# Sheet1.net
KiCad netlist of a schematic drawn in Altium Designer
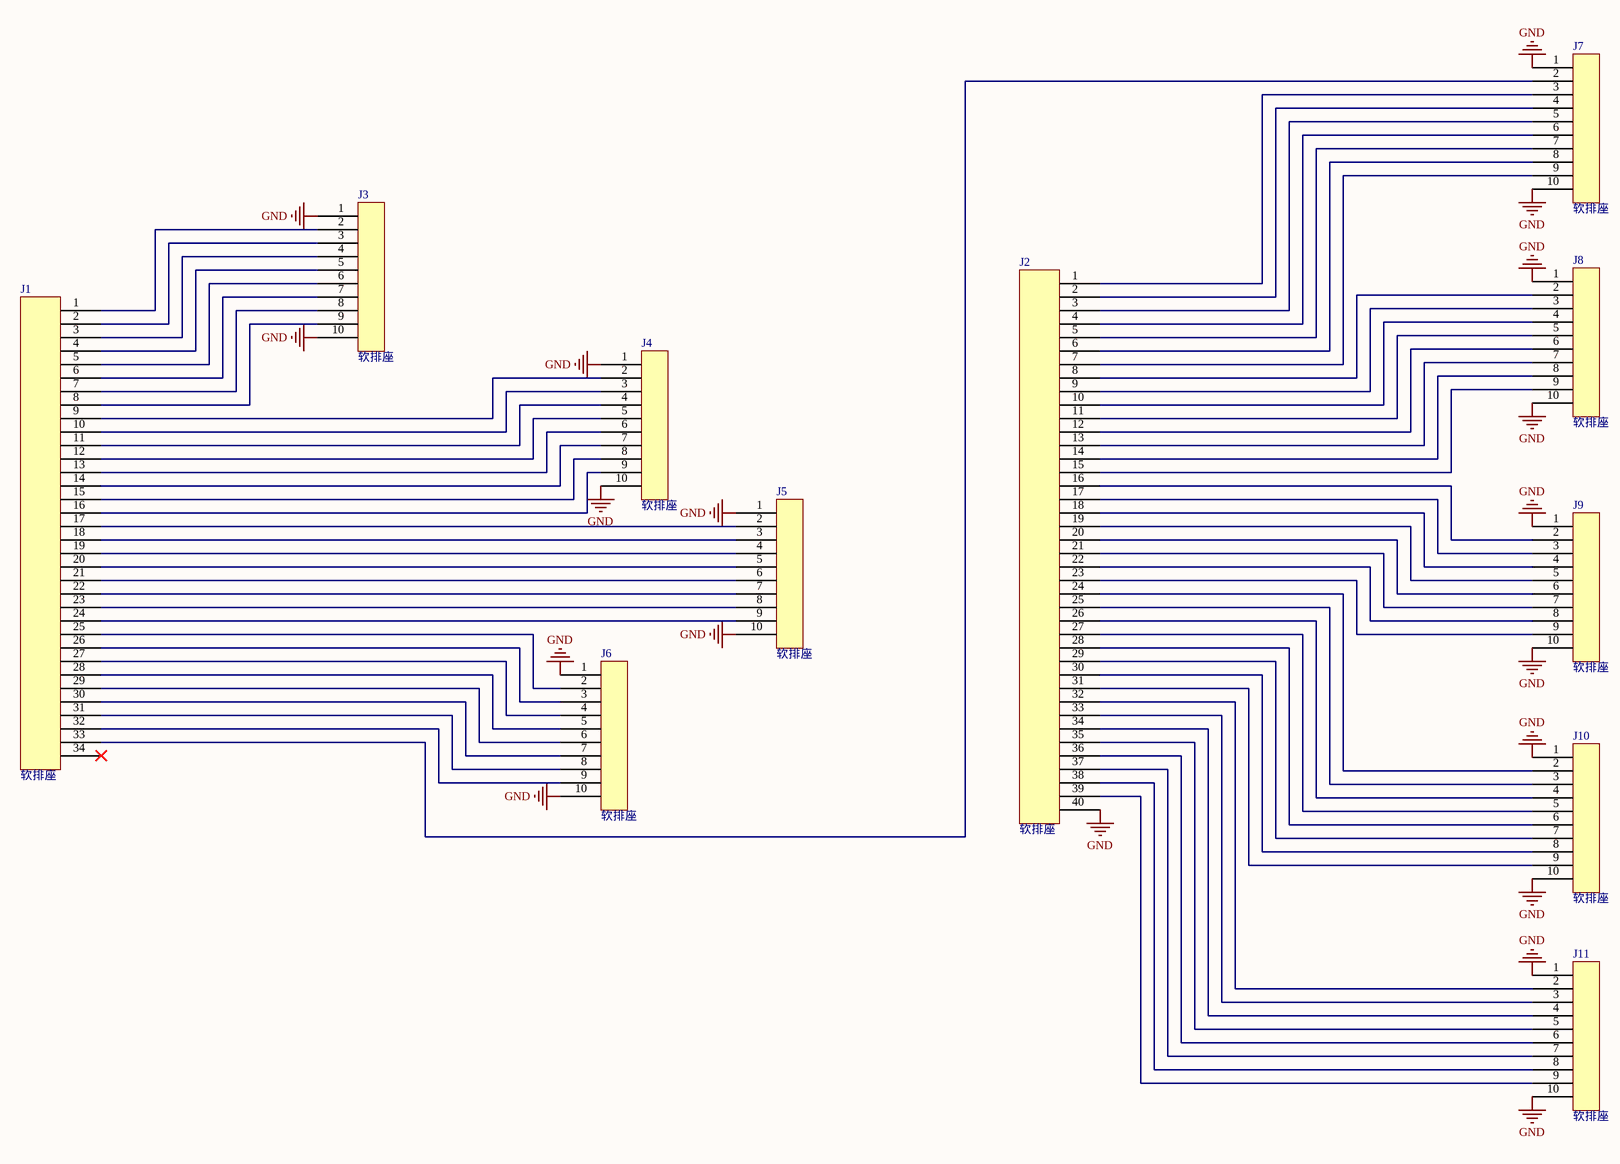
[diagram p0: Sheet1.SchDoc]

(export (version "E")
  (design (tool "Eeschema 10.0.6"))
  (components
    (comp (ref "J1") (value "软排座") (footprint "34P软排线") (libsource (lib "My") (part "34P")))
    (comp (ref "J2") (value "软排座") (footprint "40P软排线") (libsource (lib "My") (part "40P")))
    (comp (ref "J3") (value "软排座") (footprint "10P软排线(逆)") (libsource (lib "My") (part "10P")))
    (comp (ref "J4") (value "软排座") (footprint "10P软排线(逆)") (libsource (lib "My") (part "10P")))
    (comp (ref "J5") (value "软排座") (footprint "10P软排线(逆)") (libsource (lib "My") (part "10P")))
    (comp (ref "J6") (value "软排座") (footprint "10P软排线(逆)") (libsource (lib "My") (part "10P")))
    (comp (ref "J7") (value "软排座") (footprint "10P软排线") (libsource (lib "My") (part "10P")))
    (comp (ref "J8") (value "软排座") (footprint "10P软排线") (libsource (lib "My") (part "10P")))
    (comp (ref "J9") (value "软排座") (footprint "10P软排线") (libsource (lib "My") (part "10P")))
    (comp (ref "J10") (value "软排座") (footprint "10P软排线") (libsource (lib "My") (part "10P")))
    (comp (ref "J11") (value "软排座") (footprint "10P软排线") (libsource (lib "My") (part "10P")))
  )
  (nets
    (net (code "1") (name "GND") (class "Default")
      (node (ref "J10") (pin "1") (pinfunction "1_1") (pintype "passive"))
      (node (ref "J10") (pin "10") (pinfunction "10_10") (pintype "passive"))
      (node (ref "J11") (pin "1") (pinfunction "1_1") (pintype "passive"))
      (node (ref "J11") (pin "10") (pinfunction "10_10") (pintype "passive"))
      (node (ref "J2") (pin "40") (pinfunction "40_40") (pintype "passive"))
      (node (ref "J3") (pin "1") (pinfunction "1_1") (pintype "passive"))
      (node (ref "J3") (pin "10") (pinfunction "10_10") (pintype "passive"))
      (node (ref "J4") (pin "1") (pinfunction "1_1") (pintype "passive"))
      (node (ref "J4") (pin "10") (pinfunction "10_10") (pintype "passive"))
      (node (ref "J5") (pin "1") (pinfunction "1_1") (pintype "passive"))
      (node (ref "J5") (pin "10") (pinfunction "10_10") (pintype "passive"))
      (node (ref "J6") (pin "1") (pinfunction "1_1") (pintype "passive"))
      (node (ref "J6") (pin "10") (pinfunction "10_10") (pintype "passive"))
      (node (ref "J7") (pin "1") (pinfunction "1_1") (pintype "passive"))
      (node (ref "J7") (pin "10") (pinfunction "10_10") (pintype "passive"))
      (node (ref "J8") (pin "1") (pinfunction "1_1") (pintype "passive"))
      (node (ref "J8") (pin "10") (pinfunction "10_10") (pintype "passive"))
      (node (ref "J9") (pin "1") (pinfunction "1_1") (pintype "passive"))
      (node (ref "J9") (pin "10") (pinfunction "10_10") (pintype "passive"))
    )
    (net (code "2") (name "Net-(J1-Pad1)") (class "Default")
      (node (ref "J1") (pin "1") (pinfunction "1_1") (pintype "passive"))
      (node (ref "J3") (pin "2") (pinfunction "2_2") (pintype "passive"))
    )
    (net (code "3") (name "Net-(J1-Pad2)") (class "Default")
      (node (ref "J1") (pin "2") (pinfunction "2_2") (pintype "passive"))
      (node (ref "J3") (pin "3") (pinfunction "3_3") (pintype "passive"))
    )
    (net (code "4") (name "Net-(J1-Pad3)") (class "Default")
      (node (ref "J1") (pin "3") (pinfunction "3_3") (pintype "passive"))
      (node (ref "J3") (pin "4") (pinfunction "4_4") (pintype "passive"))
    )
    (net (code "5") (name "Net-(J1-Pad4)") (class "Default")
      (node (ref "J1") (pin "4") (pinfunction "4_4") (pintype "passive"))
      (node (ref "J3") (pin "5") (pinfunction "5_5") (pintype "passive"))
    )
    (net (code "6") (name "Net-(J1-Pad5)") (class "Default")
      (node (ref "J1") (pin "5") (pinfunction "5_5") (pintype "passive"))
      (node (ref "J3") (pin "6") (pinfunction "6_6") (pintype "passive"))
    )
    (net (code "7") (name "Net-(J1-Pad6)") (class "Default")
      (node (ref "J1") (pin "6") (pinfunction "6_6") (pintype "passive"))
      (node (ref "J3") (pin "7") (pinfunction "7_7") (pintype "passive"))
    )
    (net (code "8") (name "Net-(J1-Pad7)") (class "Default")
      (node (ref "J1") (pin "7") (pinfunction "7_7") (pintype "passive"))
      (node (ref "J3") (pin "8") (pinfunction "8_8") (pintype "passive"))
    )
    (net (code "9") (name "Net-(J1-Pad8)") (class "Default")
      (node (ref "J1") (pin "8") (pinfunction "8_8") (pintype "passive"))
      (node (ref "J3") (pin "9") (pinfunction "9_9") (pintype "passive"))
    )
    (net (code "10") (name "Net-(J1-Pad9)") (class "Default")
      (node (ref "J1") (pin "9") (pinfunction "9_9") (pintype "passive"))
      (node (ref "J4") (pin "2") (pinfunction "2_2") (pintype "passive"))
    )
    (net (code "11") (name "Net-(J1-Pad10)") (class "Default")
      (node (ref "J1") (pin "10") (pinfunction "10_10") (pintype "passive"))
      (node (ref "J4") (pin "3") (pinfunction "3_3") (pintype "passive"))
    )
    (net (code "12") (name "Net-(J1-Pad11)") (class "Default")
      (node (ref "J1") (pin "11") (pinfunction "11_11") (pintype "passive"))
      (node (ref "J4") (pin "4") (pinfunction "4_4") (pintype "passive"))
    )
    (net (code "13") (name "Net-(J1-Pad12)") (class "Default")
      (node (ref "J1") (pin "12") (pinfunction "12_12") (pintype "passive"))
      (node (ref "J4") (pin "5") (pinfunction "5_5") (pintype "passive"))
    )
    (net (code "14") (name "Net-(J1-Pad13)") (class "Default")
      (node (ref "J1") (pin "13") (pinfunction "13_13") (pintype "passive"))
      (node (ref "J4") (pin "6") (pinfunction "6_6") (pintype "passive"))
    )
    (net (code "15") (name "Net-(J1-Pad14)") (class "Default")
      (node (ref "J1") (pin "14") (pinfunction "14_14") (pintype "passive"))
      (node (ref "J4") (pin "7") (pinfunction "7_7") (pintype "passive"))
    )
    (net (code "16") (name "Net-(J1-Pad15)") (class "Default")
      (node (ref "J1") (pin "15") (pinfunction "15_15") (pintype "passive"))
      (node (ref "J4") (pin "8") (pinfunction "8_8") (pintype "passive"))
    )
    (net (code "17") (name "Net-(J1-Pad16)") (class "Default")
      (node (ref "J1") (pin "16") (pinfunction "16_16") (pintype "passive"))
      (node (ref "J4") (pin "9") (pinfunction "9_9") (pintype "passive"))
    )
    (net (code "18") (name "Net-(J1-Pad17)") (class "Default")
      (node (ref "J1") (pin "17") (pinfunction "17_17") (pintype "passive"))
      (node (ref "J5") (pin "2") (pinfunction "2_2") (pintype "passive"))
    )
    (net (code "19") (name "Net-(J1-Pad18)") (class "Default")
      (node (ref "J1") (pin "18") (pinfunction "18_18") (pintype "passive"))
      (node (ref "J5") (pin "3") (pinfunction "3_3") (pintype "passive"))
    )
    (net (code "20") (name "Net-(J1-Pad19)") (class "Default")
      (node (ref "J1") (pin "19") (pinfunction "19_19") (pintype "passive"))
      (node (ref "J5") (pin "4") (pinfunction "4_4") (pintype "passive"))
    )
    (net (code "21") (name "Net-(J1-Pad20)") (class "Default")
      (node (ref "J1") (pin "20") (pinfunction "20_20") (pintype "passive"))
      (node (ref "J5") (pin "5") (pinfunction "5_5") (pintype "passive"))
    )
    (net (code "22") (name "Net-(J1-Pad21)") (class "Default")
      (node (ref "J1") (pin "21") (pinfunction "21_21") (pintype "passive"))
      (node (ref "J5") (pin "6") (pinfunction "6_6") (pintype "passive"))
    )
    (net (code "23") (name "Net-(J1-Pad22)") (class "Default")
      (node (ref "J1") (pin "22") (pinfunction "22_22") (pintype "passive"))
      (node (ref "J5") (pin "7") (pinfunction "7_7") (pintype "passive"))
    )
    (net (code "24") (name "Net-(J1-Pad23)") (class "Default")
      (node (ref "J1") (pin "23") (pinfunction "23_23") (pintype "passive"))
      (node (ref "J5") (pin "8") (pinfunction "8_8") (pintype "passive"))
    )
    (net (code "25") (name "Net-(J1-Pad24)") (class "Default")
      (node (ref "J1") (pin "24") (pinfunction "24_24") (pintype "passive"))
      (node (ref "J5") (pin "9") (pinfunction "9_9") (pintype "passive"))
    )
    (net (code "26") (name "Net-(J1-Pad25)") (class "Default")
      (node (ref "J1") (pin "25") (pinfunction "25_25") (pintype "passive"))
      (node (ref "J6") (pin "2") (pinfunction "2_2") (pintype "passive"))
    )
    (net (code "27") (name "Net-(J1-Pad26)") (class "Default")
      (node (ref "J1") (pin "26") (pinfunction "26_26") (pintype "passive"))
      (node (ref "J6") (pin "3") (pinfunction "3_3") (pintype "passive"))
    )
    (net (code "28") (name "Net-(J1-Pad27)") (class "Default")
      (node (ref "J1") (pin "27") (pinfunction "27_27") (pintype "passive"))
      (node (ref "J6") (pin "4") (pinfunction "4_4") (pintype "passive"))
    )
    (net (code "29") (name "Net-(J1-Pad28)") (class "Default")
      (node (ref "J1") (pin "28") (pinfunction "28_28") (pintype "passive"))
      (node (ref "J6") (pin "5") (pinfunction "5_5") (pintype "passive"))
    )
    (net (code "30") (name "Net-(J1-Pad29)") (class "Default")
      (node (ref "J1") (pin "29") (pinfunction "29_29") (pintype "passive"))
      (node (ref "J6") (pin "6") (pinfunction "6_6") (pintype "passive"))
    )
    (net (code "31") (name "Net-(J1-Pad30)") (class "Default")
      (node (ref "J1") (pin "30") (pinfunction "30_30") (pintype "passive"))
      (node (ref "J6") (pin "7") (pinfunction "7_7") (pintype "passive"))
    )
    (net (code "32") (name "Net-(J1-Pad31)") (class "Default")
      (node (ref "J1") (pin "31") (pinfunction "31_31") (pintype "passive"))
      (node (ref "J6") (pin "8") (pinfunction "8_8") (pintype "passive"))
    )
    (net (code "33") (name "Net-(J1-Pad32)") (class "Default")
      (node (ref "J1") (pin "32") (pinfunction "32_32") (pintype "passive"))
      (node (ref "J6") (pin "9") (pinfunction "9_9") (pintype "passive"))
    )
    (net (code "34") (name "Net-(J1-Pad33)") (class "Default")
      (node (ref "J1") (pin "33") (pinfunction "33_33") (pintype "passive"))
      (node (ref "J7") (pin "2") (pinfunction "2_2") (pintype "passive"))
    )
    (net (code "35") (name "Net-(J2-Pad1)") (class "Default")
      (node (ref "J2") (pin "1") (pinfunction "1_1") (pintype "passive"))
      (node (ref "J7") (pin "3") (pinfunction "3_3") (pintype "passive"))
    )
    (net (code "36") (name "Net-(J2-Pad2)") (class "Default")
      (node (ref "J2") (pin "2") (pinfunction "2_2") (pintype "passive"))
      (node (ref "J7") (pin "4") (pinfunction "4_4") (pintype "passive"))
    )
    (net (code "37") (name "Net-(J2-Pad3)") (class "Default")
      (node (ref "J2") (pin "3") (pinfunction "3_3") (pintype "passive"))
      (node (ref "J7") (pin "5") (pinfunction "5_5") (pintype "passive"))
    )
    (net (code "38") (name "Net-(J2-Pad4)") (class "Default")
      (node (ref "J2") (pin "4") (pinfunction "4_4") (pintype "passive"))
      (node (ref "J7") (pin "6") (pinfunction "6_6") (pintype "passive"))
    )
    (net (code "39") (name "Net-(J2-Pad5)") (class "Default")
      (node (ref "J2") (pin "5") (pinfunction "5_5") (pintype "passive"))
      (node (ref "J7") (pin "7") (pinfunction "7_7") (pintype "passive"))
    )
    (net (code "40") (name "Net-(J2-Pad6)") (class "Default")
      (node (ref "J2") (pin "6") (pinfunction "6_6") (pintype "passive"))
      (node (ref "J7") (pin "8") (pinfunction "8_8") (pintype "passive"))
    )
    (net (code "41") (name "Net-(J2-Pad7)") (class "Default")
      (node (ref "J2") (pin "7") (pinfunction "7_7") (pintype "passive"))
      (node (ref "J7") (pin "9") (pinfunction "9_9") (pintype "passive"))
    )
    (net (code "42") (name "Net-(J2-Pad8)") (class "Default")
      (node (ref "J2") (pin "8") (pinfunction "8_8") (pintype "passive"))
      (node (ref "J8") (pin "2") (pinfunction "2_2") (pintype "passive"))
    )
    (net (code "43") (name "Net-(J2-Pad9)") (class "Default")
      (node (ref "J2") (pin "9") (pinfunction "9_9") (pintype "passive"))
      (node (ref "J8") (pin "3") (pinfunction "3_3") (pintype "passive"))
    )
    (net (code "44") (name "Net-(J2-Pad10)") (class "Default")
      (node (ref "J2") (pin "10") (pinfunction "10_10") (pintype "passive"))
      (node (ref "J8") (pin "4") (pinfunction "4_4") (pintype "passive"))
    )
    (net (code "45") (name "Net-(J2-Pad11)") (class "Default")
      (node (ref "J2") (pin "11") (pinfunction "11_11") (pintype "passive"))
      (node (ref "J8") (pin "5") (pinfunction "5_5") (pintype "passive"))
    )
    (net (code "46") (name "Net-(J2-Pad12)") (class "Default")
      (node (ref "J2") (pin "12") (pinfunction "12_12") (pintype "passive"))
      (node (ref "J8") (pin "6") (pinfunction "6_6") (pintype "passive"))
    )
    (net (code "47") (name "Net-(J2-Pad13)") (class "Default")
      (node (ref "J2") (pin "13") (pinfunction "13_13") (pintype "passive"))
      (node (ref "J8") (pin "7") (pinfunction "7_7") (pintype "passive"))
    )
    (net (code "48") (name "Net-(J2-Pad14)") (class "Default")
      (node (ref "J2") (pin "14") (pinfunction "14_14") (pintype "passive"))
      (node (ref "J8") (pin "8") (pinfunction "8_8") (pintype "passive"))
    )
    (net (code "49") (name "Net-(J2-Pad15)") (class "Default")
      (node (ref "J2") (pin "15") (pinfunction "15_15") (pintype "passive"))
      (node (ref "J8") (pin "9") (pinfunction "9_9") (pintype "passive"))
    )
    (net (code "50") (name "Net-(J2-Pad16)") (class "Default")
      (node (ref "J2") (pin "16") (pinfunction "16_16") (pintype "passive"))
      (node (ref "J9") (pin "2") (pinfunction "2_2") (pintype "passive"))
    )
    (net (code "51") (name "Net-(J2-Pad17)") (class "Default")
      (node (ref "J2") (pin "17") (pinfunction "17_17") (pintype "passive"))
      (node (ref "J9") (pin "3") (pinfunction "3_3") (pintype "passive"))
    )
    (net (code "52") (name "Net-(J2-Pad18)") (class "Default")
      (node (ref "J2") (pin "18") (pinfunction "18_18") (pintype "passive"))
      (node (ref "J9") (pin "4") (pinfunction "4_4") (pintype "passive"))
    )
    (net (code "53") (name "Net-(J2-Pad19)") (class "Default")
      (node (ref "J2") (pin "19") (pinfunction "19_19") (pintype "passive"))
      (node (ref "J9") (pin "5") (pinfunction "5_5") (pintype "passive"))
    )
    (net (code "54") (name "Net-(J2-Pad20)") (class "Default")
      (node (ref "J2") (pin "20") (pinfunction "20_20") (pintype "passive"))
      (node (ref "J9") (pin "6") (pinfunction "6_6") (pintype "passive"))
    )
    (net (code "55") (name "Net-(J2-Pad21)") (class "Default")
      (node (ref "J2") (pin "21") (pinfunction "21_21") (pintype "passive"))
      (node (ref "J9") (pin "7") (pinfunction "7_7") (pintype "passive"))
    )
    (net (code "56") (name "Net-(J2-Pad22)") (class "Default")
      (node (ref "J2") (pin "22") (pinfunction "22_22") (pintype "passive"))
      (node (ref "J9") (pin "8") (pinfunction "8_8") (pintype "passive"))
    )
    (net (code "57") (name "Net-(J2-Pad23)") (class "Default")
      (node (ref "J2") (pin "23") (pinfunction "23_23") (pintype "passive"))
      (node (ref "J9") (pin "9") (pinfunction "9_9") (pintype "passive"))
    )
    (net (code "58") (name "Net-(J10-Pad2)") (class "Default")
      (node (ref "J10") (pin "2") (pinfunction "2_2") (pintype "passive"))
      (node (ref "J2") (pin "24") (pinfunction "24_24") (pintype "passive"))
    )
    (net (code "59") (name "Net-(J10-Pad3)") (class "Default")
      (node (ref "J10") (pin "3") (pinfunction "3_3") (pintype "passive"))
      (node (ref "J2") (pin "25") (pinfunction "25_25") (pintype "passive"))
    )
    (net (code "60") (name "Net-(J10-Pad4)") (class "Default")
      (node (ref "J10") (pin "4") (pinfunction "4_4") (pintype "passive"))
      (node (ref "J2") (pin "26") (pinfunction "26_26") (pintype "passive"))
    )
    (net (code "61") (name "Net-(J10-Pad5)") (class "Default")
      (node (ref "J10") (pin "5") (pinfunction "5_5") (pintype "passive"))
      (node (ref "J2") (pin "27") (pinfunction "27_27") (pintype "passive"))
    )
    (net (code "62") (name "Net-(J10-Pad6)") (class "Default")
      (node (ref "J10") (pin "6") (pinfunction "6_6") (pintype "passive"))
      (node (ref "J2") (pin "28") (pinfunction "28_28") (pintype "passive"))
    )
    (net (code "63") (name "Net-(J10-Pad7)") (class "Default")
      (node (ref "J10") (pin "7") (pinfunction "7_7") (pintype "passive"))
      (node (ref "J2") (pin "29") (pinfunction "29_29") (pintype "passive"))
    )
    (net (code "64") (name "Net-(J10-Pad8)") (class "Default")
      (node (ref "J10") (pin "8") (pinfunction "8_8") (pintype "passive"))
      (node (ref "J2") (pin "30") (pinfunction "30_30") (pintype "passive"))
    )
    (net (code "65") (name "Net-(J10-Pad9)") (class "Default")
      (node (ref "J10") (pin "9") (pinfunction "9_9") (pintype "passive"))
      (node (ref "J2") (pin "31") (pinfunction "31_31") (pintype "passive"))
    )
    (net (code "66") (name "Net-(J11-Pad2)") (class "Default")
      (node (ref "J11") (pin "2") (pinfunction "2_2") (pintype "passive"))
      (node (ref "J2") (pin "32") (pinfunction "32_32") (pintype "passive"))
    )
    (net (code "67") (name "Net-(J11-Pad3)") (class "Default")
      (node (ref "J11") (pin "3") (pinfunction "3_3") (pintype "passive"))
      (node (ref "J2") (pin "33") (pinfunction "33_33") (pintype "passive"))
    )
    (net (code "68") (name "Net-(J11-Pad4)") (class "Default")
      (node (ref "J11") (pin "4") (pinfunction "4_4") (pintype "passive"))
      (node (ref "J2") (pin "34") (pinfunction "34_34") (pintype "passive"))
    )
    (net (code "69") (name "Net-(J11-Pad5)") (class "Default")
      (node (ref "J11") (pin "5") (pinfunction "5_5") (pintype "passive"))
      (node (ref "J2") (pin "35") (pinfunction "35_35") (pintype "passive"))
    )
    (net (code "70") (name "Net-(J11-Pad6)") (class "Default")
      (node (ref "J11") (pin "6") (pinfunction "6_6") (pintype "passive"))
      (node (ref "J2") (pin "36") (pinfunction "36_36") (pintype "passive"))
    )
    (net (code "71") (name "Net-(J11-Pad7)") (class "Default")
      (node (ref "J11") (pin "7") (pinfunction "7_7") (pintype "passive"))
      (node (ref "J2") (pin "37") (pinfunction "37_37") (pintype "passive"))
    )
    (net (code "72") (name "Net-(J11-Pad8)") (class "Default")
      (node (ref "J11") (pin "8") (pinfunction "8_8") (pintype "passive"))
      (node (ref "J2") (pin "38") (pinfunction "38_38") (pintype "passive"))
    )
    (net (code "73") (name "Net-(J11-Pad9)") (class "Default")
      (node (ref "J11") (pin "9") (pinfunction "9_9") (pintype "passive"))
      (node (ref "J2") (pin "39") (pinfunction "39_39") (pintype "passive"))
    )
    (net (code "74") (name "unconnected-(J1-Pad34)") (class "Default")
      (node (ref "J1") (pin "34") (pinfunction "34_34") (pintype "passive+no_connect"))
    )
  )
)
